# rel_ladder.net
KiCad netlist of a schematic drawn in Altium Designer
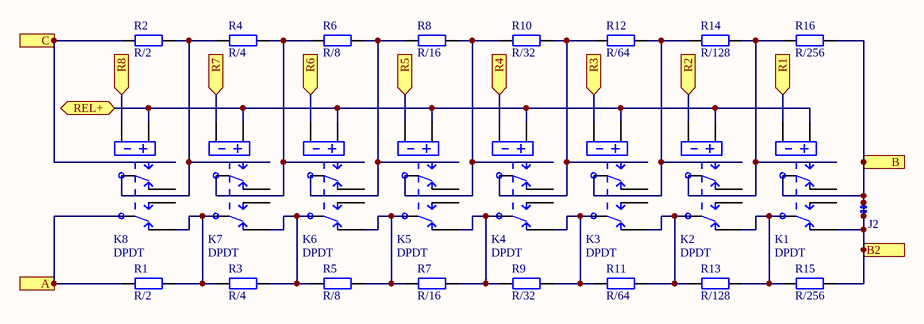
[diagram p0: rel_ladder.SchDoc]

(export (version "E")
  (design (tool "Eeschema 10.0.6"))
  (components
    (comp (ref "J2")
      (value "JMP_mini")
      (footprint "solderJumper")
      (libsource (lib "Kon_Tipk") (part "JMP_mini"))
    )
    (comp (ref "K1")
      (value "DPDT")
      (footprint "AXICOM IM-G Relay")
      (description "TE CONNECTIVITY  IM-GR  RELAY, DPDT, NO")
      (libsource (lib "DistopikAltiumLibrary") (part "IM-GR Relay DPDT"))
    )
    (comp (ref "K2")
      (value "DPDT")
      (footprint "AXICOM IM-G Relay")
      (description "TE CONNECTIVITY  IM-GR  RELAY, DPDT, NO")
      (libsource (lib "DistopikAltiumLibrary") (part "IM-GR Relay DPDT"))
    )
    (comp (ref "K3")
      (value "DPDT")
      (footprint "AXICOM IM-G Relay")
      (description "TE CONNECTIVITY  IM-GR  RELAY, DPDT, NO")
      (libsource (lib "DistopikAltiumLibrary") (part "IM-GR Relay DPDT"))
    )
    (comp (ref "K4")
      (value "DPDT")
      (footprint "AXICOM IM-G Relay")
      (description "TE CONNECTIVITY  IM-GR  RELAY, DPDT, NO")
      (libsource (lib "DistopikAltiumLibrary") (part "IM-GR Relay DPDT"))
    )
    (comp (ref "K5")
      (value "DPDT")
      (footprint "AXICOM IM-G Relay")
      (description "TE CONNECTIVITY  IM-GR  RELAY, DPDT, NO")
      (libsource (lib "DistopikAltiumLibrary") (part "IM-GR Relay DPDT"))
    )
    (comp (ref "K6")
      (value "DPDT")
      (footprint "AXICOM IM-G Relay")
      (description "TE CONNECTIVITY  IM-GR  RELAY, DPDT, NO")
      (libsource (lib "DistopikAltiumLibrary") (part "IM-GR Relay DPDT"))
    )
    (comp (ref "K7")
      (value "DPDT")
      (footprint "AXICOM IM-G Relay")
      (description "TE CONNECTIVITY  IM-GR  RELAY, DPDT, NO")
      (libsource (lib "DistopikAltiumLibrary") (part "IM-GR Relay DPDT"))
    )
    (comp (ref "K8")
      (value "DPDT")
      (footprint "AXICOM IM-G Relay")
      (description "TE CONNECTIVITY  IM-GR  RELAY, DPDT, NO")
      (libsource (lib "DistopikAltiumLibrary") (part "IM-GR Relay DPDT"))
    )
    (comp (ref "R1")
      (value "R/2")
      (footprint "R2012_0805I_L")
      (description "R")
      (libsource (lib "General") (part "R"))
    )
    (comp (ref "R2")
      (value "R/2")
      (footprint "R2012_0805I_L")
      (description "R")
      (libsource (lib "General") (part "R"))
    )
    (comp (ref "R3")
      (value "R/4")
      (footprint "R2012_0805I_L")
      (description "R")
      (libsource (lib "General") (part "R"))
    )
    (comp (ref "R4")
      (value "R/4")
      (footprint "R2012_0805I_L")
      (description "R")
      (libsource (lib "General") (part "R"))
    )
    (comp (ref "R5")
      (value "R/8")
      (footprint "R2012_0805I_L")
      (description "R")
      (libsource (lib "General") (part "R"))
    )
    (comp (ref "R6")
      (value "R/8")
      (footprint "R2012_0805I_L")
      (description "R")
      (libsource (lib "General") (part "R"))
    )
    (comp (ref "R7")
      (value "R/16")
      (footprint "R2012_0805I_L")
      (description "R")
      (libsource (lib "General") (part "R"))
    )
    (comp (ref "R8")
      (value "R/16")
      (footprint "R2012_0805I_L")
      (description "R")
      (libsource (lib "General") (part "R"))
    )
    (comp (ref "R9")
      (value "R/32")
      (footprint "R2012_0805I_L")
      (description "R")
      (libsource (lib "General") (part "R"))
    )
    (comp (ref "R10")
      (value "R/32")
      (footprint "R2012_0805I_L")
      (description "R")
      (libsource (lib "General") (part "R"))
    )
    (comp (ref "R11")
      (value "R/64")
      (footprint "R2012_0805I_L")
      (description "R")
      (libsource (lib "General") (part "R"))
    )
    (comp (ref "R12")
      (value "R/64")
      (footprint "R2012_0805I_L")
      (description "R")
      (libsource (lib "General") (part "R"))
    )
    (comp (ref "R13")
      (value "R/128")
      (footprint "R2012_0805I_L")
      (description "R")
      (libsource (lib "General") (part "R"))
    )
    (comp (ref "R14")
      (value "R/128")
      (footprint "R2012_0805I_L")
      (description "R")
      (libsource (lib "General") (part "R"))
    )
    (comp (ref "R15")
      (value "R/256")
      (footprint "R2012_0805I_L")
      (description "R")
      (libsource (lib "General") (part "R"))
    )
    (comp (ref "R16")
      (value "R/256")
      (footprint "R2012_0805I_L")
      (description "R")
      (libsource (lib "General") (part "R"))
    )
  )
  (nets
    (net (code "1") (name "/A") (class "Default")
      (node (ref "K8") (pin "6") (pinfunction "6_6") (pintype "passive"))
      (node (ref "R1") (pin "1") (pintype "passive"))
    )
    (net (code "2") (name "/B") (class "Default")
      (node (ref "J2") (pin "1") (pinfunction "1_1") (pintype "passive"))
      (node (ref "J2") (pin "2") (pinfunction "2_2") (pintype "passive"))
      (node (ref "K1") (pin "3") (pinfunction "3_3") (pintype "passive"))
      (node (ref "K1") (pin "7") (pinfunction "7_7") (pintype "passive"))
      (node (ref "R15") (pin "2") (pintype "passive"))
      (node (ref "R16") (pin "2") (pintype "passive"))
    )
    (net (code "3") (name "/C") (class "Default")
      (node (ref "K8") (pin "4") (pinfunction "4_4") (pintype "passive"))
      (node (ref "R2") (pin "1") (pintype "passive"))
    )
    (net (code "4") (name "/R1") (class "Default")
      (node (ref "K1") (pin "8") (pinfunction "8_8") (pintype "passive"))
    )
    (net (code "5") (name "/R2") (class "Default")
      (node (ref "K2") (pin "8") (pinfunction "8_8") (pintype "passive"))
    )
    (net (code "6") (name "/R3") (class "Default")
      (node (ref "K3") (pin "8") (pinfunction "8_8") (pintype "passive"))
    )
    (net (code "7") (name "/R4") (class "Default")
      (node (ref "K4") (pin "8") (pinfunction "8_8") (pintype "passive"))
    )
    (net (code "8") (name "/R5") (class "Default")
      (node (ref "K5") (pin "8") (pinfunction "8_8") (pintype "passive"))
    )
    (net (code "9") (name "/R6") (class "Default")
      (node (ref "K6") (pin "8") (pinfunction "8_8") (pintype "passive"))
    )
    (net (code "10") (name "/R7") (class "Default")
      (node (ref "K7") (pin "8") (pinfunction "8_8") (pintype "passive"))
    )
    (net (code "11") (name "/R8") (class "Default")
      (node (ref "K8") (pin "8") (pinfunction "8_8") (pintype "passive"))
    )
    (net (code "12") (name "/REL+") (class "Default")
      (node (ref "K1") (pin "1") (pinfunction "1_1") (pintype "passive"))
      (node (ref "K2") (pin "1") (pinfunction "1_1") (pintype "passive"))
      (node (ref "K3") (pin "1") (pinfunction "1_1") (pintype "passive"))
      (node (ref "K4") (pin "1") (pinfunction "1_1") (pintype "passive"))
      (node (ref "K5") (pin "1") (pinfunction "1_1") (pintype "passive"))
      (node (ref "K6") (pin "1") (pinfunction "1_1") (pintype "passive"))
      (node (ref "K7") (pin "1") (pinfunction "1_1") (pintype "passive"))
      (node (ref "K8") (pin "1") (pinfunction "1_1") (pintype "passive"))
    )
    (net (code "13") (name "Net-(K1-Pad4)") (class "Default")
      (node (ref "K1") (pin "4") (pinfunction "4_4") (pintype "passive"))
      (node (ref "K2") (pin "3") (pinfunction "3_3") (pintype "passive"))
      (node (ref "R14") (pin "2") (pintype "passive"))
      (node (ref "R16") (pin "1") (pintype "passive"))
    )
    (net (code "14") (name "Net-(K1-Pad6)") (class "Default")
      (node (ref "K1") (pin "6") (pinfunction "6_6") (pintype "passive"))
      (node (ref "K2") (pin "7") (pinfunction "7_7") (pintype "passive"))
      (node (ref "R13") (pin "2") (pintype "passive"))
      (node (ref "R15") (pin "1") (pintype "passive"))
    )
    (net (code "15") (name "Net-(K2-Pad4)") (class "Default")
      (node (ref "K2") (pin "4") (pinfunction "4_4") (pintype "passive"))
      (node (ref "K3") (pin "3") (pinfunction "3_3") (pintype "passive"))
      (node (ref "R12") (pin "2") (pintype "passive"))
      (node (ref "R14") (pin "1") (pintype "passive"))
    )
    (net (code "16") (name "Net-(K2-Pad6)") (class "Default")
      (node (ref "K2") (pin "6") (pinfunction "6_6") (pintype "passive"))
      (node (ref "K3") (pin "7") (pinfunction "7_7") (pintype "passive"))
      (node (ref "R11") (pin "2") (pintype "passive"))
      (node (ref "R13") (pin "1") (pintype "passive"))
    )
    (net (code "17") (name "Net-(K3-Pad4)") (class "Default")
      (node (ref "K3") (pin "4") (pinfunction "4_4") (pintype "passive"))
      (node (ref "K4") (pin "3") (pinfunction "3_3") (pintype "passive"))
      (node (ref "R10") (pin "2") (pintype "passive"))
      (node (ref "R12") (pin "1") (pintype "passive"))
    )
    (net (code "18") (name "Net-(K3-Pad6)") (class "Default")
      (node (ref "K3") (pin "6") (pinfunction "6_6") (pintype "passive"))
      (node (ref "K4") (pin "7") (pinfunction "7_7") (pintype "passive"))
      (node (ref "R11") (pin "1") (pintype "passive"))
      (node (ref "R9") (pin "2") (pintype "passive"))
    )
    (net (code "19") (name "Net-(K4-Pad4)") (class "Default")
      (node (ref "K4") (pin "4") (pinfunction "4_4") (pintype "passive"))
      (node (ref "K5") (pin "3") (pinfunction "3_3") (pintype "passive"))
      (node (ref "R10") (pin "1") (pintype "passive"))
      (node (ref "R8") (pin "2") (pintype "passive"))
    )
    (net (code "20") (name "Net-(K4-Pad6)") (class "Default")
      (node (ref "K4") (pin "6") (pinfunction "6_6") (pintype "passive"))
      (node (ref "K5") (pin "7") (pinfunction "7_7") (pintype "passive"))
      (node (ref "R7") (pin "2") (pintype "passive"))
      (node (ref "R9") (pin "1") (pintype "passive"))
    )
    (net (code "21") (name "Net-(K5-Pad4)") (class "Default")
      (node (ref "K5") (pin "4") (pinfunction "4_4") (pintype "passive"))
      (node (ref "K6") (pin "3") (pinfunction "3_3") (pintype "passive"))
      (node (ref "R6") (pin "2") (pintype "passive"))
      (node (ref "R8") (pin "1") (pintype "passive"))
    )
    (net (code "22") (name "Net-(K5-Pad6)") (class "Default")
      (node (ref "K5") (pin "6") (pinfunction "6_6") (pintype "passive"))
      (node (ref "K6") (pin "7") (pinfunction "7_7") (pintype "passive"))
      (node (ref "R5") (pin "2") (pintype "passive"))
      (node (ref "R7") (pin "1") (pintype "passive"))
    )
    (net (code "23") (name "Net-(K6-Pad4)") (class "Default")
      (node (ref "K6") (pin "4") (pinfunction "4_4") (pintype "passive"))
      (node (ref "K7") (pin "3") (pinfunction "3_3") (pintype "passive"))
      (node (ref "R4") (pin "2") (pintype "passive"))
      (node (ref "R6") (pin "1") (pintype "passive"))
    )
    (net (code "24") (name "Net-(K6-Pad6)") (class "Default")
      (node (ref "K6") (pin "6") (pinfunction "6_6") (pintype "passive"))
      (node (ref "K7") (pin "7") (pinfunction "7_7") (pintype "passive"))
      (node (ref "R3") (pin "2") (pintype "passive"))
      (node (ref "R5") (pin "1") (pintype "passive"))
    )
    (net (code "25") (name "Net-(K7-Pad4)") (class "Default")
      (node (ref "K7") (pin "4") (pinfunction "4_4") (pintype "passive"))
      (node (ref "K8") (pin "3") (pinfunction "3_3") (pintype "passive"))
      (node (ref "R2") (pin "2") (pintype "passive"))
      (node (ref "R4") (pin "1") (pintype "passive"))
    )
    (net (code "26") (name "Net-(K7-Pad6)") (class "Default")
      (node (ref "K7") (pin "6") (pinfunction "6_6") (pintype "passive"))
      (node (ref "K8") (pin "7") (pinfunction "7_7") (pintype "passive"))
      (node (ref "R1") (pin "2") (pintype "passive"))
      (node (ref "R3") (pin "1") (pintype "passive"))
    )
    (net (code "27") (name "unconnected-(K1-Pad2)") (class "Default")
      (node (ref "K1") (pin "2") (pinfunction "2_2") (pintype "passive"))
    )
    (net (code "28") (name "unconnected-(K1-Pad5)") (class "Default")
      (node (ref "K1") (pin "5") (pinfunction "5_5") (pintype "passive"))
    )
    (net (code "29") (name "unconnected-(K2-Pad2)") (class "Default")
      (node (ref "K2") (pin "2") (pinfunction "2_2") (pintype "passive"))
    )
    (net (code "30") (name "unconnected-(K2-Pad5)") (class "Default")
      (node (ref "K2") (pin "5") (pinfunction "5_5") (pintype "passive"))
    )
    (net (code "31") (name "unconnected-(K3-Pad2)") (class "Default")
      (node (ref "K3") (pin "2") (pinfunction "2_2") (pintype "passive"))
    )
    (net (code "32") (name "unconnected-(K3-Pad5)") (class "Default")
      (node (ref "K3") (pin "5") (pinfunction "5_5") (pintype "passive"))
    )
    (net (code "33") (name "unconnected-(K4-Pad2)") (class "Default")
      (node (ref "K4") (pin "2") (pinfunction "2_2") (pintype "passive"))
    )
    (net (code "34") (name "unconnected-(K4-Pad5)") (class "Default")
      (node (ref "K4") (pin "5") (pinfunction "5_5") (pintype "passive"))
    )
    (net (code "35") (name "unconnected-(K5-Pad2)") (class "Default")
      (node (ref "K5") (pin "2") (pinfunction "2_2") (pintype "passive"))
    )
    (net (code "36") (name "unconnected-(K5-Pad5)") (class "Default")
      (node (ref "K5") (pin "5") (pinfunction "5_5") (pintype "passive"))
    )
    (net (code "37") (name "unconnected-(K6-Pad2)") (class "Default")
      (node (ref "K6") (pin "2") (pinfunction "2_2") (pintype "passive"))
    )
    (net (code "38") (name "unconnected-(K6-Pad5)") (class "Default")
      (node (ref "K6") (pin "5") (pinfunction "5_5") (pintype "passive"))
    )
    (net (code "39") (name "unconnected-(K7-Pad2)") (class "Default")
      (node (ref "K7") (pin "2") (pinfunction "2_2") (pintype "passive"))
    )
    (net (code "40") (name "unconnected-(K7-Pad5)") (class "Default")
      (node (ref "K7") (pin "5") (pinfunction "5_5") (pintype "passive"))
    )
    (net (code "41") (name "unconnected-(K8-Pad2)") (class "Default")
      (node (ref "K8") (pin "2") (pinfunction "2_2") (pintype "passive"))
    )
    (net (code "42") (name "unconnected-(K8-Pad5)") (class "Default")
      (node (ref "K8") (pin "5") (pinfunction "5_5") (pintype "passive"))
    )
  )
)
